# CLK_GEN.net
KiCad netlist of a schematic drawn in Altium Designer
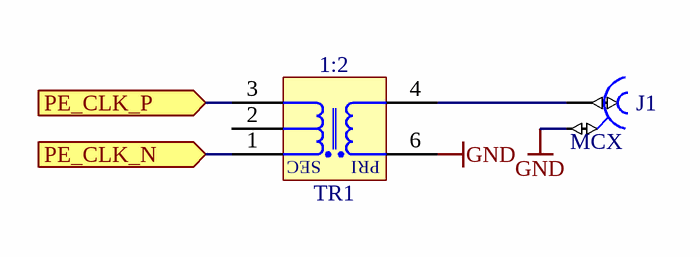
[diagram p0: CLK_GEN.SchDoc]

(export (version "E")
  (design (tool "Eeschema 10.0.6"))
  (components
    (comp (ref "J1")
      (value "MCX")
      (footprint "AMPHENOL_919-383J-51A")
      (fields
        (field (name "PART NUMBER") "AMPHENOL_919-383J-51A")
        (field (name "MANUFACTURER") "AMPHENOL")
        (field (name "MANUFACTURER PART NUMBER") "919-383J-51A")
        (field (name "AUTHOR") "CERN DEM BC")
      )
      (libsource (lib "Connectors") (part "Coax_1Female_1Shield"))
    )
    (comp (ref "TR1")
      (value "1:2")
      (footprint "XFMR_MINI-CIRCUITS_DB714")
      (description "50 Ohms 3 to 300MHz RF Transformer")
      (fields
        (field (name "PART NUMBER") "XFMR_MINI-CIRCUITS_TCM2-1T")
        (field (name "POWER") "0.25W")
        (field (name "AUTHOR") "CERN DEM HF")
      )
      (libsource (lib "Inductors & Transformers") (part "XFMR_MINI-CIRCUITS_TCM2-1T"))
    )
  )
  (nets
    (net (code "1") (name "/PE_CLK_N") (class "Default")
      (node (ref "TR1") (pin "1") (pinfunction "SDOT_1") (pintype "passive"))
    )
    (net (code "2") (name "/PE_CLK_P") (class "Default")
      (node (ref "TR1") (pin "3") (pinfunction "S_3") (pintype "passive"))
    )
    (net (code "3") (name "GND") (class "Default")
      (node (ref "J1") (pin "2") (pinfunction "2_2") (pintype "bidirectional"))
      (node (ref "TR1") (pin "6") (pinfunction "PDOT_6") (pintype "passive"))
    )
    (net (code "4") (name "Net-(TR1-P)") (class "Default")
      (node (ref "J1") (pin "1") (pinfunction "1_1") (pintype "bidirectional"))
      (node (ref "TR1") (pin "4") (pinfunction "P_4") (pintype "passive"))
    )
    (net (code "5") (name "unconnected-(TR1-NU-Pad2)") (class "Default")
      (node (ref "TR1") (pin "2") (pinfunction "NU_2") (pintype "passive"))
    )
  )
)
